# 12_B_TO_B.net
KiCad netlist of a schematic drawn in Altium Designer
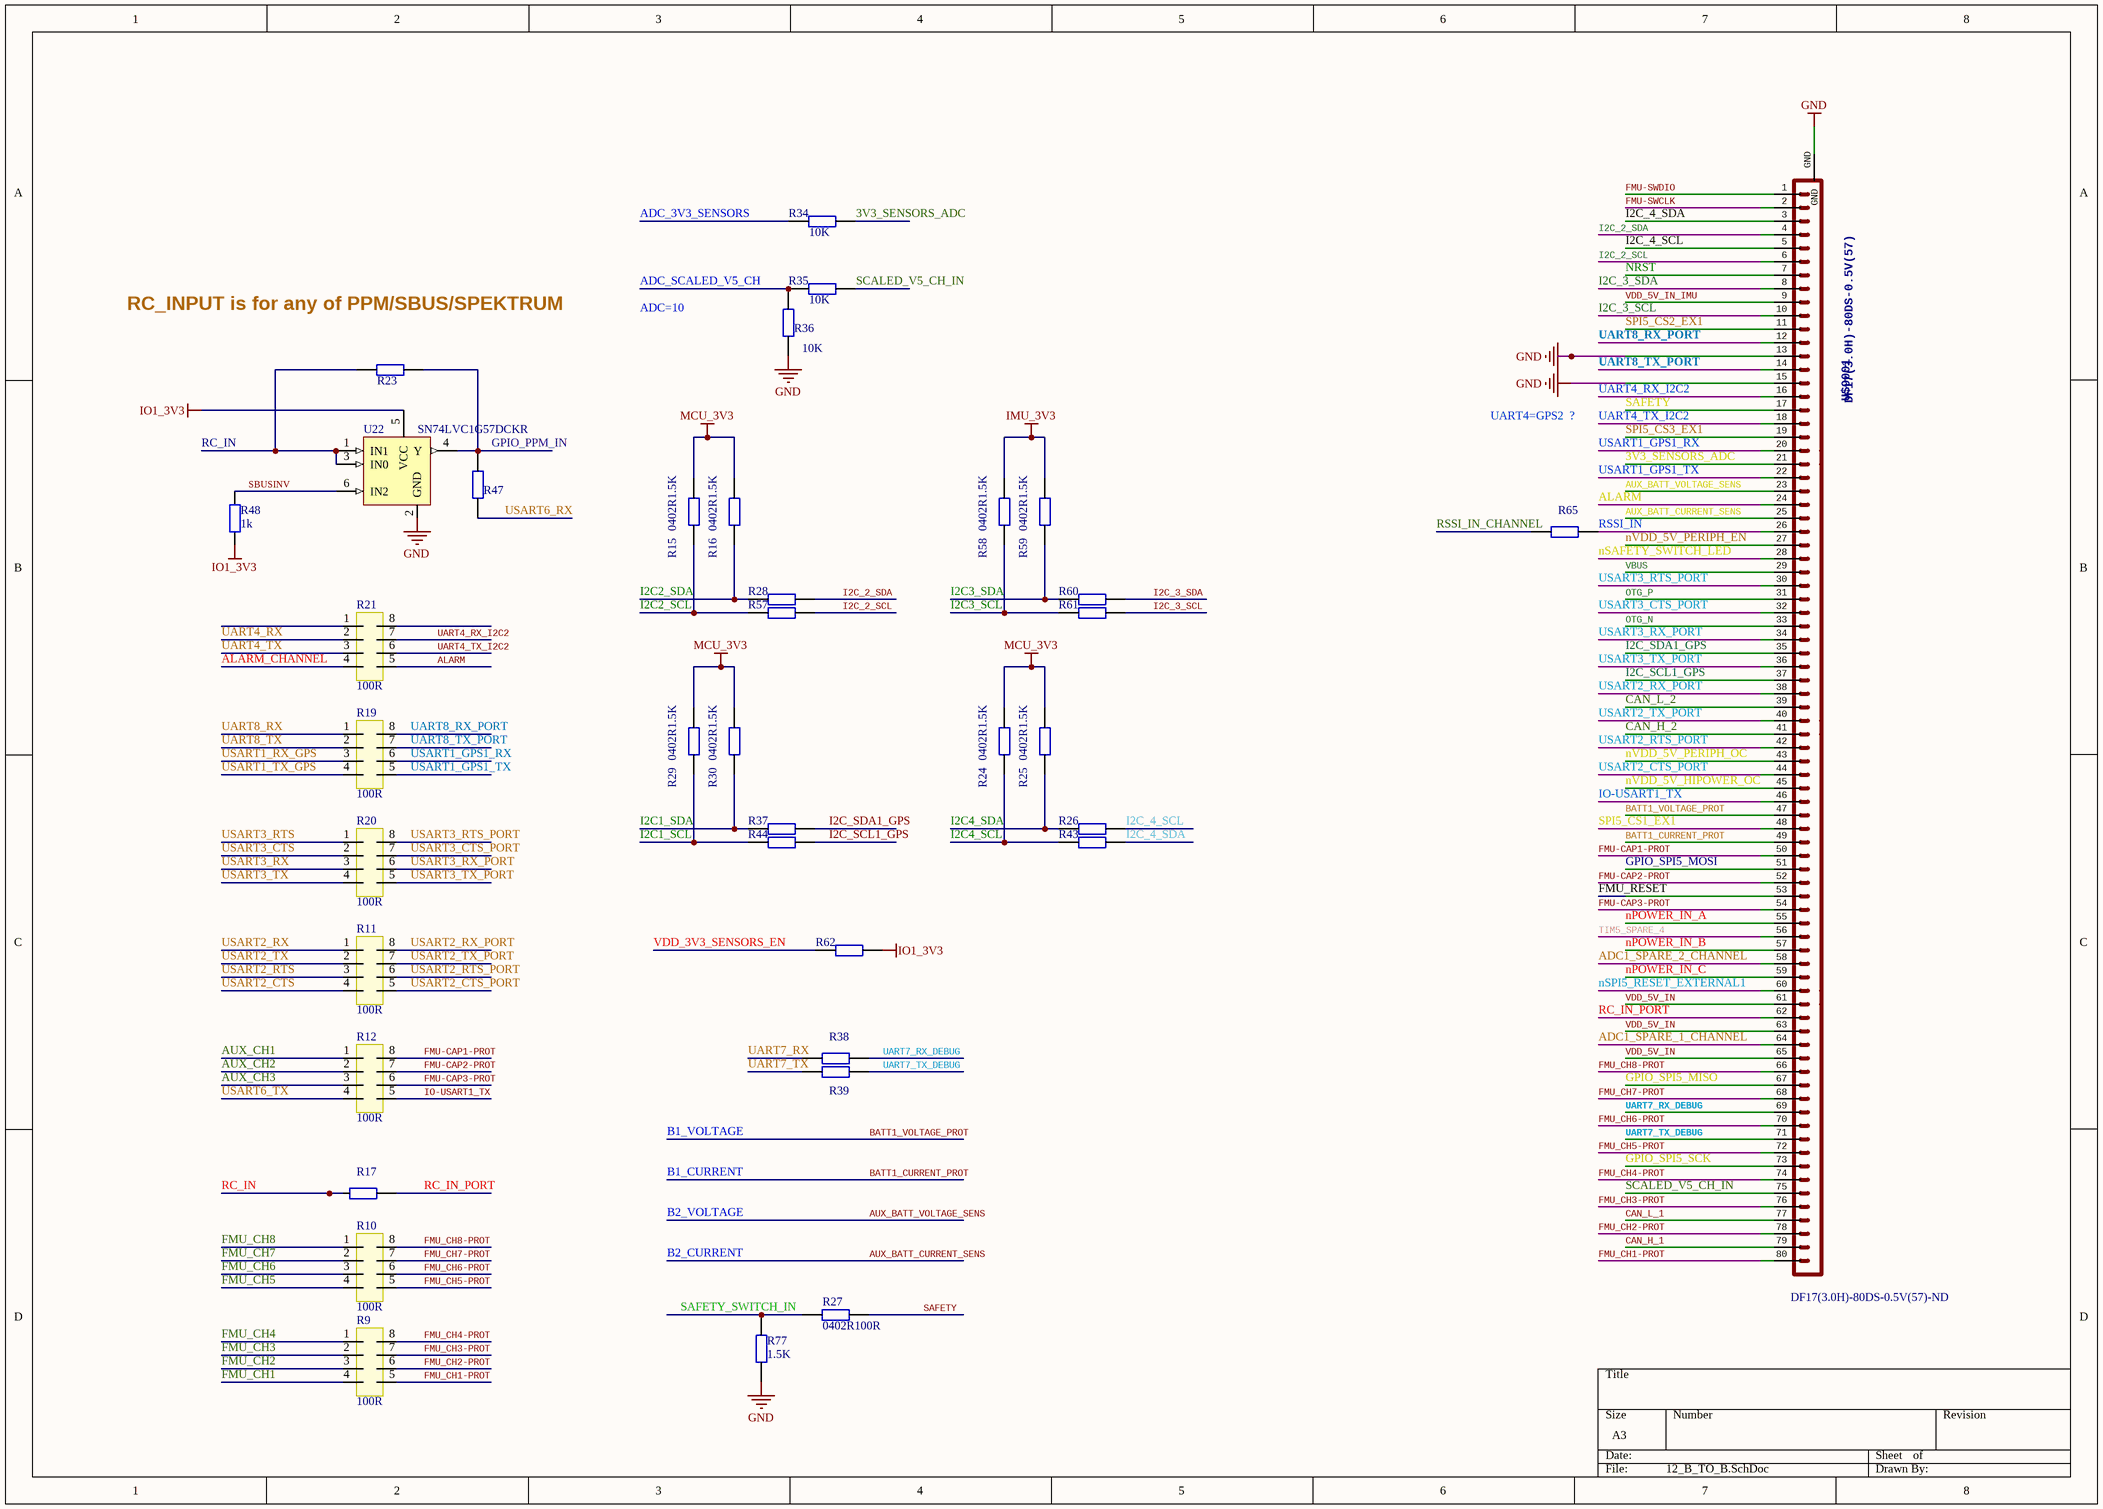
[diagram p0: 12_B_TO_B.SchDoc]

(export (version "E")
  (design (tool "Eeschema 10.0.6"))
  (components
    (comp (ref "R9") (value "100R") (footprint "0402_4r") (libsource (lib "CUAV") (part "0402-8R-4R")))
    (comp (ref "R10") (value "100R") (footprint "0402_4r") (libsource (lib "CUAV") (part "0402-8R-4R")))
    (comp (ref "R11") (value "100R") (footprint "0402_4r") (libsource (lib "CUAV") (part "0402-8R-4R")))
    (comp (ref "R12") (value "100R") (footprint "0402_4r") (libsource (lib "CUAV") (part "0402-8R-4R")))
    (comp (ref "R15")
      (value "0402R1.5K")
      (footprint "0402R")
      (description "0402R10K 1%")
      (libsource (lib "CUAV") (part "0402R10K"))
    )
    (comp (ref "R16")
      (value "0402R1.5K")
      (footprint "0402R")
      (description "0402R10K 1%")
      (libsource (lib "CUAV") (part "0402R10K"))
    )
    (comp (ref "R17")
      (value "0402R100R")
      (footprint "0402R")
      (description "0402R100R 1%")
      (libsource (lib "CUAV") (part "0402R100R"))
    )
    (comp (ref "R19") (value "100R") (footprint "0402_4r") (libsource (lib "CUAV") (part "0402-8R-4R")))
    (comp (ref "R20") (value "100R") (footprint "0402_4r") (libsource (lib "CUAV") (part "0402-8R-4R")))
    (comp (ref "R21") (value "100R") (footprint "0402_4r") (libsource (lib "CUAV") (part "0402-8R-4R")))
    (comp (ref "R23")
      (value "100R/NC")
      (footprint "0402R")
      (description "0402R100R 1%")
      (libsource (lib "") (part "0402R100R_2"))
    )
    (comp (ref "R24")
      (value "0402R1.5K")
      (footprint "0402R")
      (description "0402R10K 1%")
      (libsource (lib "CUAV") (part "0402R10K"))
    )
    (comp (ref "R25")
      (value "0402R1.5K")
      (footprint "0402R")
      (description "0402R10K 1%")
      (libsource (lib "CUAV") (part "0402R10K"))
    )
    (comp (ref "R26")
      (value "0402R100R")
      (footprint "0402R")
      (description "0402R100R 1%")
      (libsource (lib "CUAV") (part "0402R100R"))
    )
    (comp (ref "R27")
      (value "0402R100R")
      (footprint "0402R")
      (description "0402R100R 1%")
      (libsource (lib "CUAV") (part "0402R100R"))
    )
    (comp (ref "R28")
      (value "0402R100R")
      (footprint "0402R")
      (description "0402R100R 1%")
      (libsource (lib "CUAV") (part "0402R100R"))
    )
    (comp (ref "R29")
      (value "0402R1.5K")
      (footprint "0402R")
      (description "0402R10K 1%")
      (libsource (lib "CUAV") (part "0402R10K"))
    )
    (comp (ref "R30")
      (value "0402R1.5K")
      (footprint "0402R")
      (description "0402R10K 1%")
      (libsource (lib "CUAV") (part "0402R10K"))
    )
    (comp (ref "R34")
      (value "10K")
      (footprint "0402R")
      (description "0402R100R 1%")
      (libsource (lib "CUAV") (part "0402R100R"))
    )
    (comp (ref "R35")
      (value "10K")
      (footprint "0402R")
      (description "0402R100R 1%")
      (libsource (lib "CUAV") (part "0402R100R"))
    )
    (comp (ref "R36")
      (value "10K")
      (footprint "0402R")
      (description "0402R100R 1%")
      (libsource (lib "") (part "0402R100R_1"))
    )
    (comp (ref "R37")
      (value "0402R100R")
      (footprint "0402R")
      (description "0402R100R 1%")
      (libsource (lib "CUAV") (part "0402R100R"))
    )
    (comp (ref "R38")
      (value "0402R100R")
      (footprint "0402R")
      (description "0402R100R 1%")
      (libsource (lib "CUAV") (part "0402R100R"))
    )
    (comp (ref "R39")
      (value "0402R100R")
      (footprint "0402R")
      (description "0402R100R 1%")
      (libsource (lib "CUAV") (part "0402R100R"))
    )
    (comp (ref "R43")
      (value "0402R100R")
      (footprint "0402R")
      (description "0402R100R 1%")
      (libsource (lib "CUAV") (part "0402R100R"))
    )
    (comp (ref "R44")
      (value "0402R100R")
      (footprint "0402R")
      (description "0402R100R 1%")
      (libsource (lib "CUAV") (part "0402R100R"))
    )
    (comp (ref "R47")
      (value "100R")
      (footprint "0402R")
      (description "0402R100R 1%")
      (libsource (lib "") (part "0402R100R_1"))
    )
    (comp (ref "R48")
      (value "1k")
      (description "Resistor")
      (fields (field (name "PUBLISHER") "Altium Limited"))
      (libsource (lib "Miscellaneous Devices") (part "Res2"))
    )
    (comp (ref "R57")
      (value "0402R100R")
      (footprint "0402R")
      (description "0402R100R 1%")
      (libsource (lib "CUAV") (part "0402R100R"))
    )
    (comp (ref "R58")
      (value "0402R1.5K")
      (footprint "0402R")
      (description "0402R10K 1%")
      (libsource (lib "CUAV") (part "0402R10K"))
    )
    (comp (ref "R59")
      (value "0402R1.5K")
      (footprint "0402R")
      (description "0402R10K 1%")
      (libsource (lib "CUAV") (part "0402R10K"))
    )
    (comp (ref "R60")
      (value "0402R100R")
      (footprint "0402R")
      (description "0402R100R 1%")
      (libsource (lib "CUAV") (part "0402R100R"))
    )
    (comp (ref "R61")
      (value "0402R100R")
      (footprint "0402R")
      (description "0402R100R 1%")
      (libsource (lib "CUAV") (part "0402R100R"))
    )
    (comp (ref "R62")
      (value "10K/NC")
      (footprint "0402R")
      (description "0402R100R 1%")
      (libsource (lib "CUAV") (part "0402R100R"))
    )
    (comp (ref "R65")
      (value "0402R100R")
      (footprint "0402R")
      (description "0402R100R 1%")
      (libsource (lib "CUAV") (part "0402R100R"))
    )
    (comp (ref "R77")
      (value "1.5K")
      (footprint "0402R")
      (description "0402R100R 1%")
      (libsource (lib "") (part "0402R100R_1"))
    )
    (comp (ref "U$9001")
      (value "DF17(3.0H)-80DS-0.5V(57)")
      (footprint "DF17(3.0H)-80DS-0.5V(57)")
      (fields (field (name "SUPPLIER PART NUMBER 1") "DF17(3.0H)-80DS-0.5V(57)-ND"))
      (libsource (lib "altium-import") (part "root_0_CON-DF17-80F_"))
    )
    (comp (ref "U22")
      (value "SN74LVC1G57DCKR")
      (footprint "sot323-6")
      (libsource (lib "My_Altium") (part "74LVC1G57"))
    )
  )
  (nets
    (net (code "1") (name "/3V3_SENSORS_ADC") (class "Default")
      (node (ref "R34") (pin "2") (pintype "passive"))
      (node (ref "U$9001") (pin "21") (pinfunction "21_21") (pintype "passive"))
    )
    (net (code "2") (name "/ADC1_SPARE_1_CHANNEL") (class "Default")
      (node (ref "U$9001") (pin "64") (pinfunction "64_64") (pintype "passive"))
    )
    (net (code "3") (name "/ADC1_SPARE_2_CHANNEL") (class "Default")
      (node (ref "U$9001") (pin "58") (pinfunction "58_58") (pintype "passive"))
    )
    (net (code "5") (name "/ADC_3V3_SENSORS") (class "Default")
      (node (ref "R34") (pin "1") (pintype "passive"))
    )
    (net (code "6") (name "/ADC_SCALED_V5_CH") (class "Default")
      (node (ref "R35") (pin "1") (pintype "passive"))
      (node (ref "R36") (pin "2") (pintype "passive"))
    )
    (net (code "7") (name "/ALARM") (class "Default")
      (node (ref "R21") (pin "5") (pinfunction "5_5") (pintype "passive"))
      (node (ref "U$9001") (pin "24") (pinfunction "24_24") (pintype "passive"))
    )
    (net (code "8") (name "/ALARM_CHANNEL") (class "Default")
      (node (ref "R21") (pin "4") (pinfunction "4_4") (pintype "passive"))
    )
    (net (code "9") (name "/AUX_BATT_CURRENT_SENS") (class "Default")
      (node (ref "U$9001") (pin "25") (pinfunction "25_25") (pintype "passive"))
    )
    (net (code "10") (name "/AUX_BATT_VOLTAGE_SENS") (class "Default")
      (node (ref "U$9001") (pin "23") (pinfunction "23_23") (pintype "passive"))
    )
    (net (code "11") (name "/AUX_CH1") (class "Default")
      (node (ref "R12") (pin "1") (pinfunction "1_1") (pintype "passive"))
    )
    (net (code "12") (name "/AUX_CH2") (class "Default")
      (node (ref "R12") (pin "2") (pinfunction "2_2") (pintype "passive"))
    )
    (net (code "13") (name "/AUX_CH3") (class "Default")
      (node (ref "R12") (pin "3") (pinfunction "3_3") (pintype "passive"))
    )
    (net (code "14") (name "/B1_CURRENT") (class "Default")
      (node (ref "U$9001") (pin "49") (pinfunction "49_49") (pintype "passive"))
    )
    (net (code "15") (name "/B1_VOLTAGE") (class "Default")
      (node (ref "U$9001") (pin "47") (pinfunction "47_47") (pintype "passive"))
    )
    (net (code "16") (name "/CAN_H_1") (class "Default")
      (node (ref "U$9001") (pin "79") (pinfunction "79_79") (pintype "passive"))
    )
    (net (code "17") (name "/CAN_H_2") (class "Default")
      (node (ref "U$9001") (pin "41") (pinfunction "41_41") (pintype "passive"))
    )
    (net (code "18") (name "/CAN_L_1") (class "Default")
      (node (ref "U$9001") (pin "77") (pinfunction "77_77") (pintype "passive"))
    )
    (net (code "19") (name "/CAN_L_2") (class "Default")
      (node (ref "U$9001") (pin "39") (pinfunction "39_39") (pintype "passive"))
    )
    (net (code "20") (name "/FMU-CAP1-PROT") (class "Default")
      (node (ref "R12") (pin "8") (pinfunction "8_8") (pintype "passive"))
      (node (ref "U$9001") (pin "50") (pinfunction "50_50") (pintype "passive"))
    )
    (net (code "21") (name "/FMU-CAP2-PROT") (class "Default")
      (node (ref "R12") (pin "7") (pinfunction "7_7") (pintype "passive"))
      (node (ref "U$9001") (pin "52") (pinfunction "52_52") (pintype "passive"))
    )
    (net (code "22") (name "/FMU-CAP3-PROT") (class "Default")
      (node (ref "R12") (pin "6") (pinfunction "6_6") (pintype "passive"))
      (node (ref "U$9001") (pin "54") (pinfunction "54_54") (pintype "passive"))
    )
    (net (code "23") (name "/FMU-SWCLK") (class "Default")
      (node (ref "U$9001") (pin "2") (pinfunction "2_2") (pintype "passive"))
    )
    (net (code "24") (name "/FMU-SWDIO") (class "Default")
      (node (ref "U$9001") (pin "1") (pinfunction "1_1") (pintype "passive"))
    )
    (net (code "25") (name "/FMU_CH1") (class "Default")
      (node (ref "R9") (pin "4") (pinfunction "4_4") (pintype "passive"))
    )
    (net (code "26") (name "/FMU_CH1-PROT") (class "Default")
      (node (ref "R9") (pin "5") (pinfunction "5_5") (pintype "passive"))
      (node (ref "U$9001") (pin "80") (pinfunction "80_80") (pintype "passive"))
    )
    (net (code "27") (name "/FMU_CH2") (class "Default")
      (node (ref "R9") (pin "3") (pinfunction "3_3") (pintype "passive"))
    )
    (net (code "28") (name "/FMU_CH2-PROT") (class "Default")
      (node (ref "R9") (pin "6") (pinfunction "6_6") (pintype "passive"))
      (node (ref "U$9001") (pin "78") (pinfunction "78_78") (pintype "passive"))
    )
    (net (code "29") (name "/FMU_CH3") (class "Default")
      (node (ref "R9") (pin "2") (pinfunction "2_2") (pintype "passive"))
    )
    (net (code "30") (name "/FMU_CH3-PROT") (class "Default")
      (node (ref "R9") (pin "7") (pinfunction "7_7") (pintype "passive"))
      (node (ref "U$9001") (pin "76") (pinfunction "76_76") (pintype "passive"))
    )
    (net (code "31") (name "/FMU_CH4") (class "Default")
      (node (ref "R9") (pin "1") (pinfunction "1_1") (pintype "passive"))
    )
    (net (code "32") (name "/FMU_CH4-PROT") (class "Default")
      (node (ref "R9") (pin "8") (pinfunction "8_8") (pintype "passive"))
      (node (ref "U$9001") (pin "74") (pinfunction "74_74") (pintype "passive"))
    )
    (net (code "33") (name "/FMU_CH5") (class "Default")
      (node (ref "R10") (pin "4") (pinfunction "4_4") (pintype "passive"))
    )
    (net (code "34") (name "/FMU_CH5-PROT") (class "Default")
      (node (ref "R10") (pin "5") (pinfunction "5_5") (pintype "passive"))
      (node (ref "U$9001") (pin "72") (pinfunction "72_72") (pintype "passive"))
    )
    (net (code "35") (name "/FMU_CH6") (class "Default")
      (node (ref "R10") (pin "3") (pinfunction "3_3") (pintype "passive"))
    )
    (net (code "36") (name "/FMU_CH6-PROT") (class "Default")
      (node (ref "R10") (pin "6") (pinfunction "6_6") (pintype "passive"))
      (node (ref "U$9001") (pin "70") (pinfunction "70_70") (pintype "passive"))
    )
    (net (code "37") (name "/FMU_CH7") (class "Default")
      (node (ref "R10") (pin "2") (pinfunction "2_2") (pintype "passive"))
    )
    (net (code "38") (name "/FMU_CH7-PROT") (class "Default")
      (node (ref "R10") (pin "7") (pinfunction "7_7") (pintype "passive"))
      (node (ref "U$9001") (pin "68") (pinfunction "68_68") (pintype "passive"))
    )
    (net (code "39") (name "/FMU_CH8") (class "Default")
      (node (ref "R10") (pin "1") (pinfunction "1_1") (pintype "passive"))
    )
    (net (code "40") (name "/FMU_CH8-PROT") (class "Default")
      (node (ref "R10") (pin "8") (pinfunction "8_8") (pintype "passive"))
      (node (ref "U$9001") (pin "66") (pinfunction "66_66") (pintype "passive"))
    )
    (net (code "41") (name "/FMU_RESET") (class "Default")
      (node (ref "U$9001") (pin "53") (pinfunction "53_53") (pintype "passive"))
    )
    (net (code "42") (name "/GPIO_PPM_IN") (class "Default")
      (node (ref "R23") (pin "1") (pintype "passive"))
      (node (ref "R47") (pin "2") (pintype "passive"))
      (node (ref "U22") (pin "4") (pinfunction "Y_4") (pintype "output"))
    )
    (net (code "43") (name "/GPIO_SPI5_MISO") (class "Default")
      (node (ref "U$9001") (pin "67") (pinfunction "67_67") (pintype "passive"))
    )
    (net (code "44") (name "/GPIO_SPI5_MOSI") (class "Default")
      (node (ref "U$9001") (pin "51") (pinfunction "51_51") (pintype "passive"))
    )
    (net (code "45") (name "/GPIO_SPI5_SCK") (class "Default")
      (node (ref "U$9001") (pin "73") (pinfunction "73_73") (pintype "passive"))
    )
    (net (code "46") (name "/I2C1_SCL") (class "Default")
      (node (ref "R29") (pin "1") (pintype "passive"))
      (node (ref "R44") (pin "1") (pintype "passive"))
    )
    (net (code "47") (name "/I2C1_SDA") (class "Default")
      (node (ref "R30") (pin "1") (pintype "passive"))
      (node (ref "R37") (pin "1") (pintype "passive"))
    )
    (net (code "48") (name "/I2C2_SCL") (class "Default")
      (node (ref "R15") (pin "1") (pintype "passive"))
      (node (ref "R57") (pin "1") (pintype "passive"))
    )
    (net (code "49") (name "/I2C2_SDA") (class "Default")
      (node (ref "R16") (pin "1") (pintype "passive"))
      (node (ref "R28") (pin "1") (pintype "passive"))
    )
    (net (code "50") (name "/I2C3_SCL") (class "Default")
      (node (ref "R58") (pin "1") (pintype "passive"))
      (node (ref "R61") (pin "1") (pintype "passive"))
    )
    (net (code "51") (name "/I2C3_SDA") (class "Default")
      (node (ref "R59") (pin "1") (pintype "passive"))
      (node (ref "R60") (pin "1") (pintype "passive"))
    )
    (net (code "52") (name "/I2C4_SCL") (class "Default")
      (node (ref "R24") (pin "1") (pintype "passive"))
      (node (ref "R43") (pin "1") (pintype "passive"))
    )
    (net (code "53") (name "/I2C4_SDA") (class "Default")
      (node (ref "R25") (pin "1") (pintype "passive"))
      (node (ref "R26") (pin "1") (pintype "passive"))
    )
    (net (code "54") (name "/I2C_2_SCL") (class "Default")
      (node (ref "R57") (pin "2") (pintype "passive"))
      (node (ref "U$9001") (pin "6") (pinfunction "6_6") (pintype "passive"))
    )
    (net (code "55") (name "/I2C_2_SDA") (class "Default")
      (node (ref "R28") (pin "2") (pintype "passive"))
      (node (ref "U$9001") (pin "4") (pinfunction "4_4") (pintype "passive"))
    )
    (net (code "56") (name "/I2C_3_SCL") (class "Default")
      (node (ref "R61") (pin "2") (pintype "passive"))
      (node (ref "U$9001") (pin "10") (pinfunction "10_10") (pintype "passive"))
    )
    (net (code "57") (name "/I2C_3_SDA") (class "Default")
      (node (ref "R60") (pin "2") (pintype "passive"))
      (node (ref "U$9001") (pin "8") (pinfunction "8_8") (pintype "passive"))
    )
    (net (code "58") (name "/I2C_4_SCL") (class "Default")
      (node (ref "R26") (pin "2") (pintype "passive"))
      (node (ref "U$9001") (pin "5") (pinfunction "5_5") (pintype "passive"))
    )
    (net (code "59") (name "/I2C_4_SDA") (class "Default")
      (node (ref "R43") (pin "2") (pintype "passive"))
      (node (ref "U$9001") (pin "3") (pinfunction "3_3") (pintype "passive"))
    )
    (net (code "60") (name "/I2C_SCL1_GPS") (class "Default")
      (node (ref "R44") (pin "2") (pintype "passive"))
      (node (ref "U$9001") (pin "37") (pinfunction "37_37") (pintype "passive"))
    )
    (net (code "61") (name "/I2C_SDA1_GPS") (class "Default")
      (node (ref "R37") (pin "2") (pintype "passive"))
      (node (ref "U$9001") (pin "35") (pinfunction "35_35") (pintype "passive"))
    )
    (net (code "62") (name "/IO-USART1_TX") (class "Default")
      (node (ref "R12") (pin "5") (pinfunction "5_5") (pintype "passive"))
      (node (ref "U$9001") (pin "46") (pinfunction "46_46") (pintype "passive"))
    )
    (net (code "63") (name "/NRST") (class "Default")
      (node (ref "U$9001") (pin "7") (pinfunction "7_7") (pintype "passive"))
    )
    (net (code "64") (name "/OTG_N") (class "Default")
      (node (ref "U$9001") (pin "33") (pinfunction "33_33") (pintype "passive"))
    )
    (net (code "65") (name "/OTG_P") (class "Default")
      (node (ref "U$9001") (pin "31") (pinfunction "31_31") (pintype "passive"))
    )
    (net (code "66") (name "/RC_IN") (class "Default")
      (node (ref "R17") (pin "1") (pintype "passive"))
      (node (ref "R23") (pin "2") (pintype "passive"))
      (node (ref "U22") (pin "1") (pinfunction "IN1_1") (pintype "input"))
      (node (ref "U22") (pin "3") (pinfunction "IN0_3") (pintype "input"))
    )
    (net (code "67") (name "/RC_IN_PORT") (class "Default")
      (node (ref "R17") (pin "2") (pintype "passive"))
      (node (ref "U$9001") (pin "62") (pinfunction "62_62") (pintype "passive"))
    )
    (net (code "68") (name "/RSSI_IN") (class "Default")
      (node (ref "R65") (pin "2") (pintype "passive"))
      (node (ref "U$9001") (pin "26") (pinfunction "26_26") (pintype "passive"))
    )
    (net (code "69") (name "/RSSI_IN_CHANNEL") (class "Default")
      (node (ref "R65") (pin "1") (pintype "passive"))
    )
    (net (code "70") (name "/SAFETY") (class "Default")
      (node (ref "R27") (pin "2") (pintype "passive"))
      (node (ref "U$9001") (pin "17") (pinfunction "17_17") (pintype "passive"))
    )
    (net (code "71") (name "/SAFETY_SWITCH_IN") (class "Default")
      (node (ref "R27") (pin "1") (pintype "passive"))
      (node (ref "R77") (pin "2") (pintype "passive"))
    )
    (net (code "72") (name "/SBUSINV") (class "Default")
      (node (ref "R48") (pin "2") (pinfunction "2_2") (pintype "passive"))
      (node (ref "U22") (pin "6") (pinfunction "IN2_6") (pintype "input"))
    )
    (net (code "73") (name "/SCALED_V5_CH_IN") (class "Default")
      (node (ref "R35") (pin "2") (pintype "passive"))
      (node (ref "U$9001") (pin "75") (pinfunction "75_75") (pintype "passive"))
    )
    (net (code "74") (name "/SPI5_CS1_EX1") (class "Default")
      (node (ref "U$9001") (pin "48") (pinfunction "48_48") (pintype "passive"))
    )
    (net (code "75") (name "/SPI5_CS2_EX1") (class "Default")
      (node (ref "U$9001") (pin "11") (pinfunction "11_11") (pintype "passive"))
    )
    (net (code "76") (name "/SPI5_CS3_EX1") (class "Default")
      (node (ref "U$9001") (pin "19") (pinfunction "19_19") (pintype "passive"))
    )
    (net (code "77") (name "/TIM5_SPARE_4") (class "Default")
      (node (ref "U$9001") (pin "56") (pinfunction "56_56") (pintype "passive"))
    )
    (net (code "79") (name "/UART4_RX") (class "Default")
      (node (ref "R21") (pin "2") (pinfunction "2_2") (pintype "passive"))
    )
    (net (code "80") (name "/UART4_RX_I2C2") (class "Default")
      (node (ref "R21") (pin "7") (pinfunction "7_7") (pintype "passive"))
      (node (ref "U$9001") (pin "16") (pinfunction "16_16") (pintype "passive"))
    )
    (net (code "81") (name "/UART4_TX") (class "Default")
      (node (ref "R21") (pin "3") (pinfunction "3_3") (pintype "passive"))
    )
    (net (code "82") (name "/UART4_TX_I2C2") (class "Default")
      (node (ref "R21") (pin "6") (pinfunction "6_6") (pintype "passive"))
      (node (ref "U$9001") (pin "18") (pinfunction "18_18") (pintype "passive"))
    )
    (net (code "83") (name "/UART7_RX") (class "Default") (node (ref "R38") (pin "1") (pintype "passive")))
    (net (code "84") (name "/UART7_RX_DEBUG") (class "Default")
      (node (ref "R38") (pin "2") (pintype "passive"))
      (node (ref "U$9001") (pin "69") (pinfunction "69_69") (pintype "passive"))
    )
    (net (code "85") (name "/UART7_TX") (class "Default") (node (ref "R39") (pin "1") (pintype "passive")))
    (net (code "86") (name "/UART7_TX_DEBUG") (class "Default")
      (node (ref "R39") (pin "2") (pintype "passive"))
      (node (ref "U$9001") (pin "71") (pinfunction "71_71") (pintype "passive"))
    )
    (net (code "87") (name "/UART8_RX") (class "Default")
      (node (ref "R19") (pin "1") (pinfunction "1_1") (pintype "passive"))
    )
    (net (code "88") (name "/UART8_RX_PORT") (class "Default")
      (node (ref "R19") (pin "8") (pinfunction "8_8") (pintype "passive"))
      (node (ref "U$9001") (pin "12") (pinfunction "12_12") (pintype "passive"))
    )
    (net (code "89") (name "/UART8_TX") (class "Default")
      (node (ref "R19") (pin "2") (pinfunction "2_2") (pintype "passive"))
    )
    (net (code "90") (name "/UART8_TX_PORT") (class "Default")
      (node (ref "R19") (pin "7") (pinfunction "7_7") (pintype "passive"))
      (node (ref "U$9001") (pin "14") (pinfunction "14_14") (pintype "passive"))
    )
    (net (code "91") (name "/USART1_GPS1_RX") (class "Default")
      (node (ref "R19") (pin "6") (pinfunction "6_6") (pintype "passive"))
      (node (ref "U$9001") (pin "20") (pinfunction "20_20") (pintype "passive"))
    )
    (net (code "92") (name "/USART1_GPS1_TX") (class "Default")
      (node (ref "R19") (pin "5") (pinfunction "5_5") (pintype "passive"))
      (node (ref "U$9001") (pin "22") (pinfunction "22_22") (pintype "passive"))
    )
    (net (code "93") (name "/USART1_RX_GPS") (class "Default")
      (node (ref "R19") (pin "3") (pinfunction "3_3") (pintype "passive"))
    )
    (net (code "94") (name "/USART1_TX_GPS") (class "Default")
      (node (ref "R19") (pin "4") (pinfunction "4_4") (pintype "passive"))
    )
    (net (code "95") (name "/USART2_CTS") (class "Default")
      (node (ref "R11") (pin "4") (pinfunction "4_4") (pintype "passive"))
    )
    (net (code "96") (name "/USART2_CTS_PORT") (class "Default")
      (node (ref "R11") (pin "5") (pinfunction "5_5") (pintype "passive"))
      (node (ref "U$9001") (pin "44") (pinfunction "44_44") (pintype "passive"))
    )
    (net (code "97") (name "/USART2_RTS") (class "Default")
      (node (ref "R11") (pin "3") (pinfunction "3_3") (pintype "passive"))
    )
    (net (code "98") (name "/USART2_RTS_PORT") (class "Default")
      (node (ref "R11") (pin "6") (pinfunction "6_6") (pintype "passive"))
      (node (ref "U$9001") (pin "42") (pinfunction "42_42") (pintype "passive"))
    )
    (net (code "99") (name "/USART2_RX") (class "Default")
      (node (ref "R11") (pin "1") (pinfunction "1_1") (pintype "passive"))
    )
    (net (code "100") (name "/USART2_RX_PORT") (class "Default")
      (node (ref "R11") (pin "8") (pinfunction "8_8") (pintype "passive"))
      (node (ref "U$9001") (pin "38") (pinfunction "38_38") (pintype "passive"))
    )
    (net (code "101") (name "/USART2_TX") (class "Default")
      (node (ref "R11") (pin "2") (pinfunction "2_2") (pintype "passive"))
    )
    (net (code "102") (name "/USART2_TX_PORT") (class "Default")
      (node (ref "R11") (pin "7") (pinfunction "7_7") (pintype "passive"))
      (node (ref "U$9001") (pin "40") (pinfunction "40_40") (pintype "passive"))
    )
    (net (code "103") (name "/USART3_CTS") (class "Default")
      (node (ref "R20") (pin "2") (pinfunction "2_2") (pintype "passive"))
    )
    (net (code "104") (name "/USART3_CTS_PORT") (class "Default")
      (node (ref "R20") (pin "7") (pinfunction "7_7") (pintype "passive"))
      (node (ref "U$9001") (pin "32") (pinfunction "32_32") (pintype "passive"))
    )
    (net (code "105") (name "/USART3_RTS") (class "Default")
      (node (ref "R20") (pin "1") (pinfunction "1_1") (pintype "passive"))
    )
    (net (code "106") (name "/USART3_RTS_PORT") (class "Default")
      (node (ref "R20") (pin "8") (pinfunction "8_8") (pintype "passive"))
      (node (ref "U$9001") (pin "30") (pinfunction "30_30") (pintype "passive"))
    )
    (net (code "107") (name "/USART3_RX") (class "Default")
      (node (ref "R20") (pin "3") (pinfunction "3_3") (pintype "passive"))
    )
    (net (code "108") (name "/USART3_RX_PORT") (class "Default")
      (node (ref "R20") (pin "6") (pinfunction "6_6") (pintype "passive"))
      (node (ref "U$9001") (pin "34") (pinfunction "34_34") (pintype "passive"))
    )
    (net (code "109") (name "/USART3_TX") (class "Default")
      (node (ref "R20") (pin "4") (pinfunction "4_4") (pintype "passive"))
    )
    (net (code "110") (name "/USART3_TX_PORT") (class "Default")
      (node (ref "R20") (pin "5") (pinfunction "5_5") (pintype "passive"))
      (node (ref "U$9001") (pin "36") (pinfunction "36_36") (pintype "passive"))
    )
    (net (code "111") (name "/USART6_RX") (class "Default") (node (ref "R47") (pin "1") (pintype "passive")))
    (net (code "112") (name "/USART6_TX") (class "Default")
      (node (ref "R12") (pin "4") (pinfunction "4_4") (pintype "passive"))
    )
    (net (code "113") (name "/VBUS") (class "Default")
      (node (ref "U$9001") (pin "29") (pinfunction "29_29") (pintype "passive"))
    )
    (net (code "114") (name "/VDD_3V3_SENSORS_EN") (class "Default")
      (node (ref "R62") (pin "1") (pintype "passive"))
    )
    (net (code "115") (name "/VDD_5V_IN") (class "Default")
      (node (ref "U$9001") (pin "61") (pinfunction "61_61") (pintype "passive"))
      (node (ref "U$9001") (pin "63") (pinfunction "63_63") (pintype "passive"))
      (node (ref "U$9001") (pin "65") (pinfunction "65_65") (pintype "passive"))
    )
    (net (code "116") (name "/VDD_5V_IN_IMU") (class "Default")
      (node (ref "U$9001") (pin "9") (pinfunction "9_9") (pintype "passive"))
    )
    (net (code "117") (name "/nPOWER_IN_A") (class "Default")
      (node (ref "U$9001") (pin "55") (pinfunction "55_55") (pintype "passive"))
    )
    (net (code "118") (name "/nPOWER_IN_B") (class "Default")
      (node (ref "U$9001") (pin "57") (pinfunction "57_57") (pintype "passive"))
    )
    (net (code "119") (name "/nPOWER_IN_C") (class "Default")
      (node (ref "U$9001") (pin "59") (pinfunction "59_59") (pintype "passive"))
    )
    (net (code "120") (name "/nSAFETY_SWITCH_LED") (class "Default")
      (node (ref "U$9001") (pin "28") (pinfunction "28_28") (pintype "passive"))
    )
    (net (code "121") (name "/nSPI5_RESET_EXTERNAL1") (class "Default")
      (node (ref "U$9001") (pin "60") (pinfunction "60_60") (pintype "passive"))
    )
    (net (code "122") (name "/nVDD_5V_HIPOWER_OC") (class "Default")
      (node (ref "U$9001") (pin "45") (pinfunction "45_45") (pintype "passive"))
    )
    (net (code "123") (name "/nVDD_5V_PERIPH_EN") (class "Default")
      (node (ref "U$9001") (pin "27") (pinfunction "27_27") (pintype "passive"))
    )
    (net (code "124") (name "/nVDD_5V_PERIPH_OC") (class "Default")
      (node (ref "U$9001") (pin "43") (pinfunction "43_43") (pintype "passive"))
    )
    (net (code "125") (name "GND") (class "Default")
      (node (ref "R36") (pin "1") (pintype "passive"))
      (node (ref "R77") (pin "1") (pintype "passive"))
      (node (ref "U$9001") (pin "13") (pinfunction "13_13") (pintype "passive"))
      (node (ref "U$9001") (pin "15") (pinfunction "15_15") (pintype "passive"))
      (node (ref "U$9001") (pin "GND") (pinfunction "GND_GND") (pintype "passive"))
      (node (ref "U22") (pin "2") (pinfunction "GND_2") (pintype "power_in"))
    )
    (net (code "126") (name "IMU_3V3") (class "Default")
      (node (ref "R58") (pin "2") (pintype "passive"))
      (node (ref "R59") (pin "2") (pintype "passive"))
    )
    (net (code "127") (name "IO1_3V3") (class "Default")
      (node (ref "R48") (pin "1") (pinfunction "1_1") (pintype "passive"))
      (node (ref "R62") (pin "2") (pintype "passive"))
      (node (ref "U22") (pin "5") (pinfunction "VCC_5") (pintype "power_in"))
    )
    (net (code "128") (name "MCU_3V3") (class "Default")
      (node (ref "R15") (pin "2") (pintype "passive"))
      (node (ref "R16") (pin "2") (pintype "passive"))
      (node (ref "R24") (pin "2") (pintype "passive"))
      (node (ref "R25") (pin "2") (pintype "passive"))
      (node (ref "R29") (pin "2") (pintype "passive"))
      (node (ref "R30") (pin "2") (pintype "passive"))
    )
    (net (code "129") (name "unconnected-(R21-Pad1)") (class "Default")
      (node (ref "R21") (pin "1") (pinfunction "1_1") (pintype "passive"))
    )
    (net (code "130") (name "unconnected-(R21-Pad8)") (class "Default")
      (node (ref "R21") (pin "8") (pinfunction "8_8") (pintype "passive"))
    )
  )
)
